# LEDs.net
KiCad netlist of a schematic drawn in Altium Designer
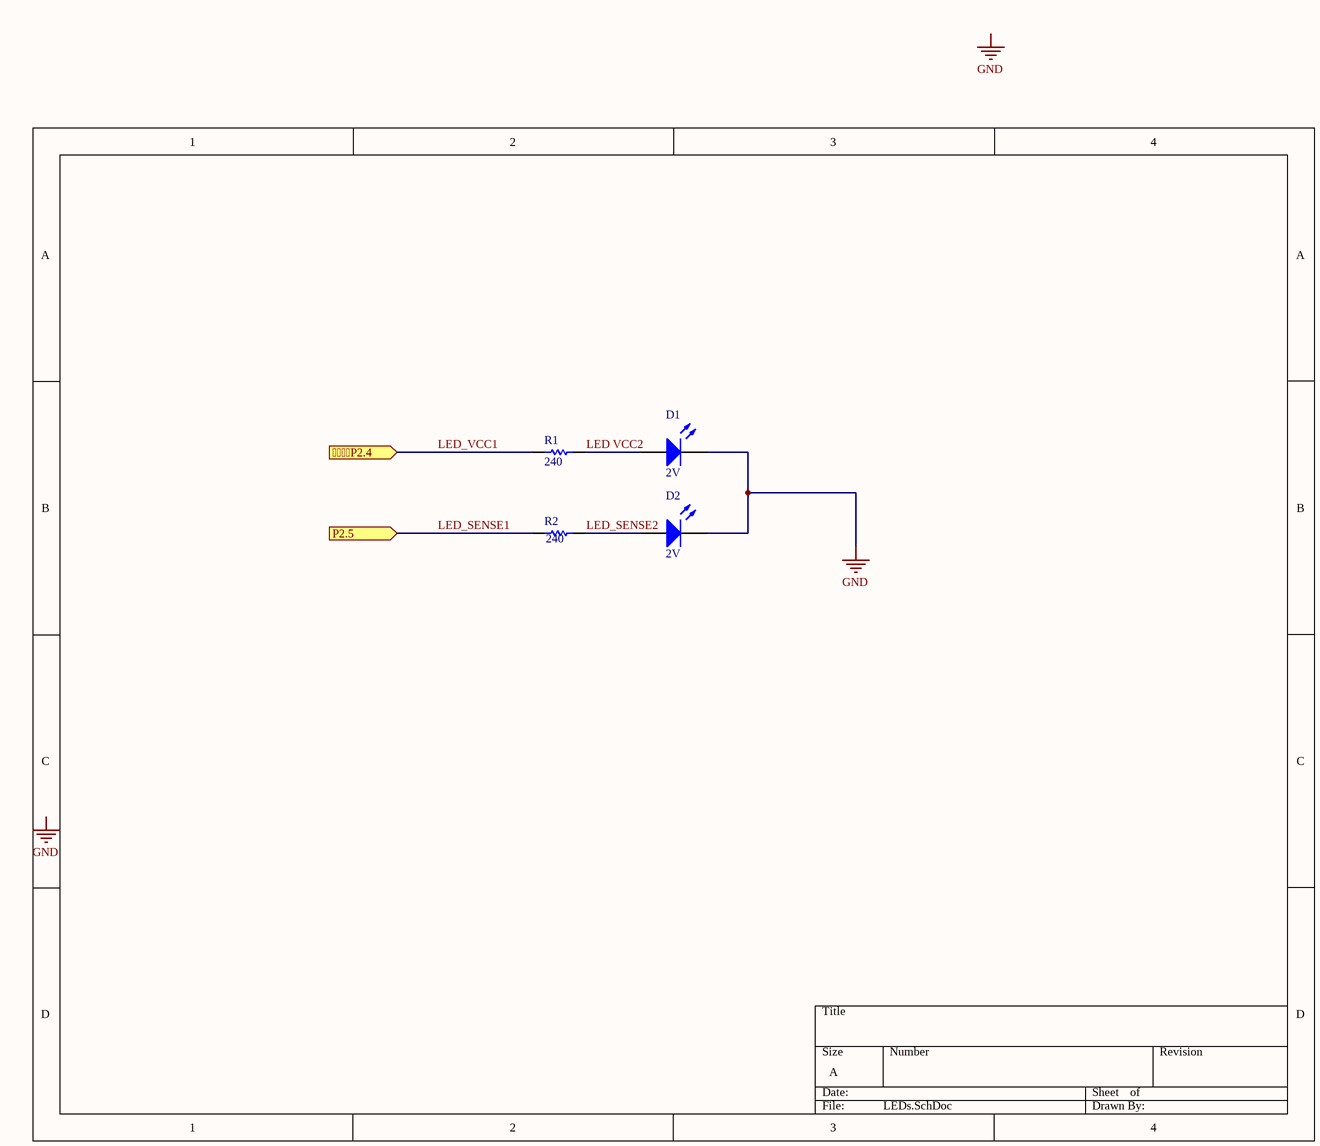
[diagram p0: LEDs.SchDoc]

(export (version "E")
  (design (tool "Eeschema 10.0.6"))
  (components
    (comp (ref "D1")
      (value "2V")
      (footprint "0805_A")
      (description "SMD mono-color Chip LED, WL-SMCW, Bright Green")
      (fields (field (name "PARTNUMBER") "150080VS75000") (field (name "MANUFACTURER") "Wuerth Elektronik"))
      (libsource (lib "Altium Content Vault") (part "WE-LED_K1A2-2"))
    )
    (comp (ref "D2")
      (value "2V")
      (footprint "0805_A")
      (description "SMD mono-color Chip LED, WL-SMCW, Bright Green")
      (fields (field (name "PARTNUMBER") "150080VS75000") (field (name "MANUFACTURER") "Wuerth Elektronik"))
      (libsource (lib "Altium Content Vault") (part "WE-LED_K1A2-2"))
    )
    (comp (ref "R1")
      (value "240")
      (footprint "RESC2013X70X40NL20T20")
      (fields (field (name "PART NUMBER") "ERJ-6ENF2400V") (field (name "MANUFACTURER") "Panasonic"))
      (libsource (lib "Altium Content Vault") (part "RES"))
    )
    (comp (ref "R2")
      (value "240")
      (footprint "RESC2013X70X40NL20T20")
      (fields (field (name "PART NUMBER") "ERJ-6ENF2400V") (field (name "MANUFACTURER") "Panasonic"))
      (libsource (lib "Altium Content Vault") (part "RES"))
    )
  )
  (nets
    (net (code "2") (name "/LED VCC2") (class "Default")
      (node (ref "D1") (pin "2") (pinfunction "A_2") (pintype "passive"))
      (node (ref "R1") (pin "2") (pinfunction "2_2") (pintype "passive"))
    )
    (net (code "3") (name "/LED_SENSE1") (class "Default")
      (node (ref "R2") (pin "1") (pinfunction "1_1") (pintype "passive"))
    )
    (net (code "4") (name "/LED_SENSE2") (class "Default")
      (node (ref "D2") (pin "2") (pinfunction "A_2") (pintype "passive"))
      (node (ref "R2") (pin "2") (pinfunction "2_2") (pintype "passive"))
    )
    (net (code "5") (name "/LED_VCC1") (class "Default")
      (node (ref "R1") (pin "1") (pinfunction "1_1") (pintype "passive"))
    )
    (net (code "6") (name "GND") (class "Default")
      (node (ref "D1") (pin "1") (pinfunction "K_1") (pintype "passive"))
      (node (ref "D2") (pin "1") (pinfunction "K_1") (pintype "passive"))
    )
  )
)
